# spi-flash.net
KiCad netlist of a schematic drawn in Altium Designer
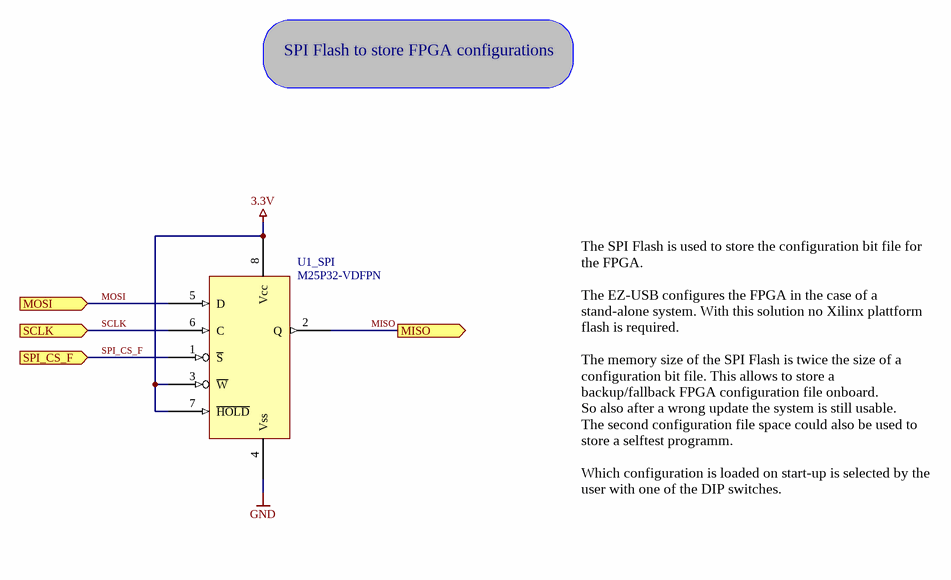
[diagram p0: spi-flash.SchDoc]

(export (version "E")
  (design (tool "Eeschema 10.0.6"))
  (components
    (comp (ref "U1_SPI")
      (value "M25P32-VDFPN")
      (footprint "VDFPN8")
      (description "Serial Flash Memory, Low Voltage, 50 MHz SPI Bus")
      (fields (field (name "MANUFACTURER") "ST") (field (name "PART NUMBER") "M25P32-VME6G"))
      (libsource (lib "*") (part "M25P32"))
    )
  )
  (nets
    (net (code "1") (name "/MISO") (class "Default")
      (node (ref "U1_SPI") (pin "2") (pinfunction "Q_2") (pintype "output"))
    )
    (net (code "2") (name "/MOSI") (class "Default")
      (node (ref "U1_SPI") (pin "5") (pinfunction "D_5") (pintype "input"))
    )
    (net (code "3") (name "/SCLK") (class "Default")
      (node (ref "U1_SPI") (pin "6") (pinfunction "C_6") (pintype "input"))
    )
    (net (code "4") (name "/SPI_CS_F") (class "Default")
      (node (ref "U1_SPI") (pin "1") (pinfunction "~{S}_1") (pintype "input"))
    )
    (net (code "5") (name "3.3V") (class "Default")
      (node (ref "U1_SPI") (pin "3") (pinfunction "~{W}_3") (pintype "input"))
      (node (ref "U1_SPI") (pin "7") (pinfunction "~{HOLD}_7") (pintype "input"))
      (node (ref "U1_SPI") (pin "8") (pinfunction "Vcc_8") (pintype "power_in"))
    )
    (net (code "6") (name "GND") (class "Default")
      (node (ref "U1_SPI") (pin "4") (pinfunction "Vss_4") (pintype "power_in"))
    )
  )
)
